# ADC.net
KiCad netlist of a schematic drawn in Altium Designer
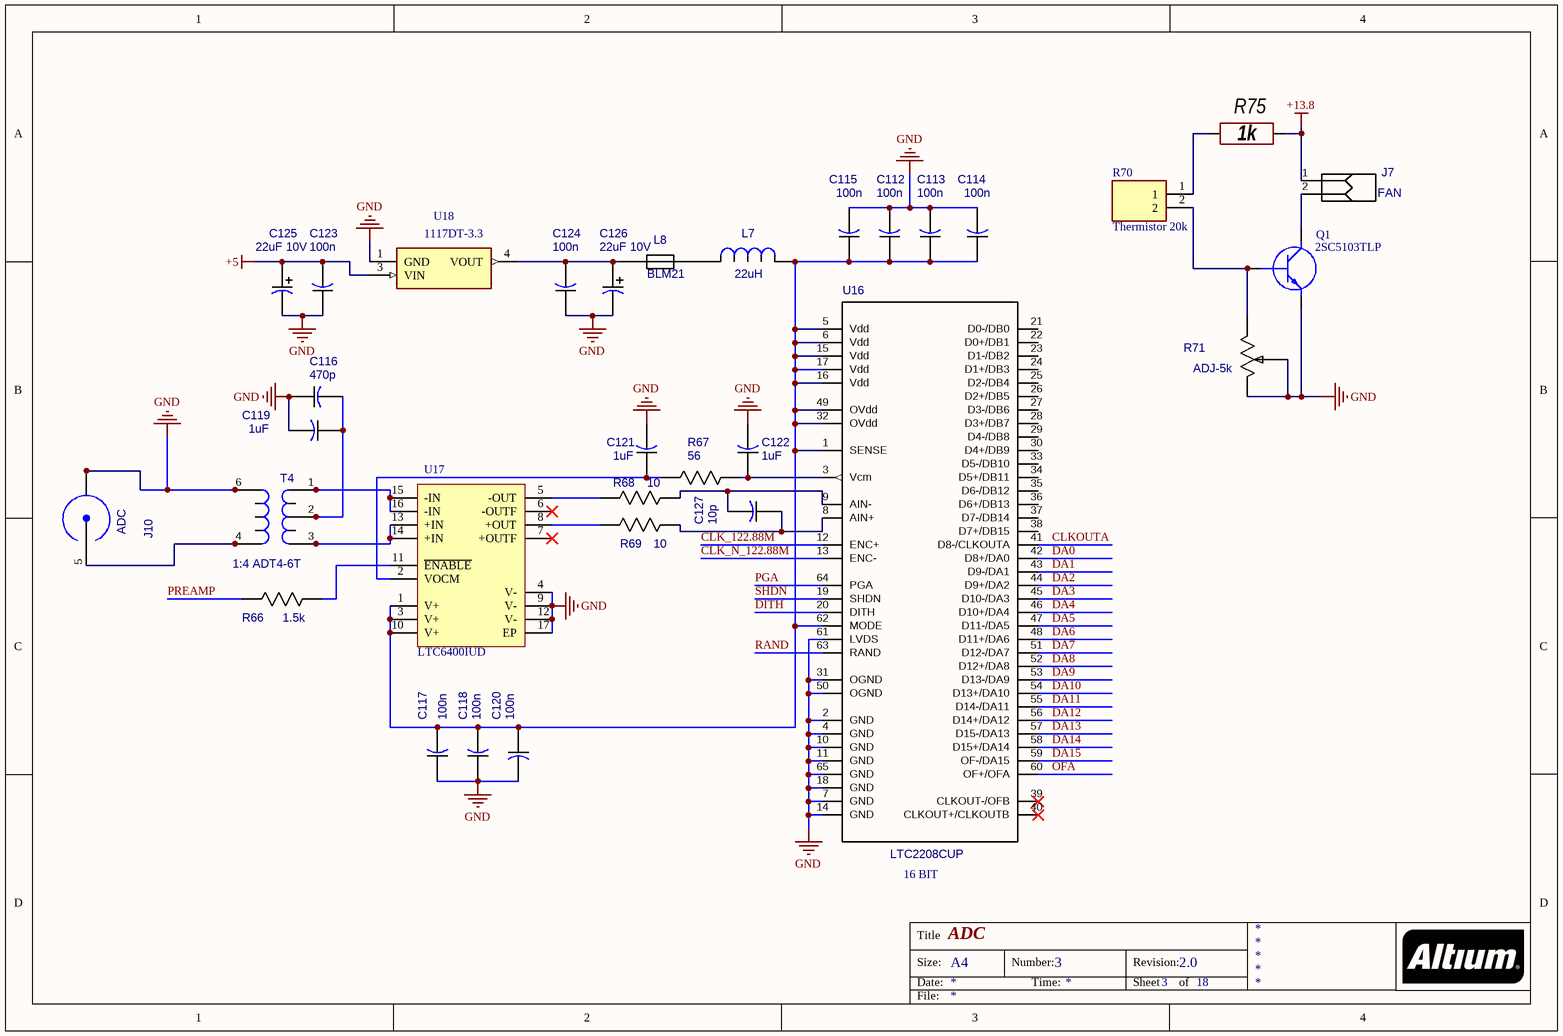
[diagram p0: ADC.SchDoc]

(export (version "E")
  (design (tool "Eeschema 10.0.6"))
  (components
    (comp (ref "C112")
      (value "100n")
      (footprint "CAP_0805")
      (description "CAP_0805")
      (libsource (lib "*") (part "CAP_0805"))
    )
    (comp (ref "C113")
      (value "100n")
      (footprint "CAP_0805")
      (description "CAP_0805")
      (libsource (lib "*") (part "CAP_0805"))
    )
    (comp (ref "C114")
      (value "100n")
      (footprint "CAP_0805")
      (description "CAP_0805")
      (libsource (lib "*") (part "CAP_0805"))
    )
    (comp (ref "C115")
      (value "100n")
      (footprint "CAP_0805")
      (description "CAP_0805")
      (libsource (lib "*") (part "CAP_0805"))
    )
    (comp (ref "C116")
      (value "470p")
      (footprint "CAP_0805")
      (description "CAP_0805")
      (libsource (lib "*") (part "CAP_0805"))
    )
    (comp (ref "C117")
      (value "100n")
      (footprint "CAP_0805")
      (description "CAP_0805")
      (libsource (lib "*") (part "CAP_0805"))
    )
    (comp (ref "C118")
      (value "100n")
      (footprint "CAP_0805")
      (description "CAP_0805")
      (libsource (lib "*") (part "CAP_0805"))
    )
    (comp (ref "C119")
      (value "1uF")
      (footprint "CAP_0805")
      (description "CAP_0805")
      (libsource (lib "*") (part "CAP_0805"))
    )
    (comp (ref "C120")
      (value "100n")
      (footprint "CAP_0805")
      (description "CAP_0805")
      (libsource (lib "*") (part "CAP_0805"))
    )
    (comp (ref "C121")
      (value "1uF")
      (footprint "CAP_0805")
      (description "CAP_0805")
      (libsource (lib "*") (part "CAP_0805"))
    )
    (comp (ref "C122")
      (value "1uF")
      (footprint "CAP_0805")
      (description "CAP_0805")
      (libsource (lib "*") (part "CAP_0805"))
    )
    (comp (ref "C123")
      (value "100n")
      (footprint "CAP_0805")
      (description "CAP_0805")
      (libsource (lib "*") (part "CAP_0805"))
    )
    (comp (ref "C124")
      (value "100n")
      (footprint "CAP_0805")
      (description "CAP_0805")
      (libsource (lib "*") (part "CAP_0805"))
    )
    (comp (ref "C125")
      (value "22uF 10V")
      (footprint "CAPAE_4.3x4.3h5.4")
      (description "CAPAE_4.3x4.3h5.4")
      (libsource (lib "MOTHERBOARD") (part "CAPAE_4.3x4.3h5.4"))
    )
    (comp (ref "C126")
      (value "22uF 10V")
      (footprint "CAPAE_4.3x4.3h5.4")
      (description "CAPAE_4.3x4.3h5.4")
      (libsource (lib "MOTHERBOARD") (part "CAPAE_4.3x4.3h5.4"))
    )
    (comp (ref "C127")
      (value "10p")
      (footprint "CAP_0805")
      (description "CAP_0805")
      (libsource (lib "*") (part "CAP_0805"))
    )
    (comp (ref "J7")
      (value "FAN")
      (footprint "51022-0200")
      (description "51022-0200")
      (libsource (lib "*") (part "51022-0200"))
    )
    (comp (ref "J10")
      (value "ADC")
      (footprint "31-5431")
      (description "SMA")
      (libsource (lib "RF-UNIT_1") (part "31-5431"))
    )
    (comp (ref "L7")
      (value "22uH")
      (footprint "IND_7x7")
      (description "IND_1206")
      (libsource (lib "*") (part "IND_1206"))
    )
    (comp (ref "L8")
      (value "BLM21")
      (footprint "CAP_0805")
      (libsource (lib "MOTHERBOARD_1") (part "IND_FERRITE_BEAD"))
    )
    (comp (ref "Q1")
      (value "2SC5103TLP")
      (footprint "SamacSys:2SC5103TLQ")
      (description "Transistor BJT NPN")
      (fields (field (name "MOUSER PART NUMBER") "755-2SC5103TLP"))
      (libsource (lib "*") (part "2SC5103TLP"))
    )
    (comp (ref "R66")
      (value "1.5k")
      (footprint "RES_0805")
      (description "RES_0805")
      (libsource (lib "*") (part "RES_0805"))
    )
    (comp (ref "R67")
      (value "56")
      (footprint "RES_0805")
      (description "RES_0805")
      (libsource (lib "") (part "RES_0805_1"))
    )
    (comp (ref "R68")
      (value "10")
      (footprint "RES_0603")
      (description "RES_0603")
      (libsource (lib "*") (part "RES_0603"))
    )
    (comp (ref "R69")
      (value "10")
      (footprint "RES_0603")
      (description "RES_0603")
      (libsource (lib "*") (part "RES_0603"))
    )
    (comp (ref "R70")
      (value "Thermistor 20k")
      (footprint "MF52A103F3950A1")
      (description "Thermistor")
      (fields (field (name "MANUFACTURER_PART_NUMBER") "MF52A103F3950(A1)"))
      (libsource (lib "*") (part "MF52A103F3950_A1_"))
    )
    (comp (ref "R71")
      (value "ADJ-5k")
      (footprint "306J")
      (description "306J")
      (libsource (lib "*") (part "306J"))
    )
    (comp (ref "R75")
      (value "1k")
      (footprint "standard:CH0805R")
      (libsource (lib "Discrete") (part "Resistor"))
    )
    (comp (ref "T4")
      (value "1:4 ADT4-6T")
      (footprint "TRANSF_ACORE2")
      (description "Transformer")
      (libsource (lib "MOTHERBOARD_1") (part "TRANSF_ACORE2"))
    )
    (comp (ref "U16") (value "LTC2208CUP") (footprint "LTC2208CUP") (libsource (lib "*") (part "LTC2208CUP")))
    (comp (ref "U17")
      (value "LTC6400IUD")
      (footprint "LT-UD-16_N")
      (fields
        (field (name "MANUFACTURER") "Linear Technology")
        (field (name "LINEAR TECHNOLOGY PART NUMBER") "LTC6400-20")
        (field (name "PARTNUMBER") "LTC6400IUD-20#PBF")
      )
      (libsource (lib "Altium Content Vault") (part "LT-LTC640X-X-16"))
    )
    (comp (ref "U18")
      (value "1117DT-3.3")
      (footprint "SamacSys:TO228P991X238-3N")
      (description "LD1117DT-2.5 DPAK")
      (fields
        (field (name "MANUFACTURER_PART_NUMBER") "LM1117DT-ADJ")
        (field (name "MOUSER PART NUMBER") "926-LM1117DT-ADJ")
      )
      (libsource (lib "*") (part "LM1117DT-ADJ"))
    )
  )
  (nets
    (net (code "1") (name "+5") (class "Default")
      (node (ref "C123") (pin "2") (pinfunction "2_2") (pintype "passive"))
      (node (ref "C125") (pin "1") (pinfunction "PLUS_1") (pintype "passive"))
      (node (ref "U18") (pin "3") (pinfunction "VIN_3") (pintype "input"))
    )
    (net (code "2") (name "+13.8") (class "Default")
      (node (ref "J7") (pin "1") (pinfunction "1_1") (pintype "passive"))
      (node (ref "R75") (pin "2") (pinfunction "2_2") (pintype "passive"))
    )
    (net (code "3") (name "/CLKOUTA") (class "Default")
      (node (ref "U16") (pin "41") (pinfunction "D8-/CLKOUTA_41") (pintype "passive"))
    )
    (net (code "4") (name "/CLK_122.88M") (class "Default")
      (node (ref "U16") (pin "12") (pinfunction "ENC+_12") (pintype "passive"))
    )
    (net (code "5") (name "/CLK_N_122.88M") (class "Default")
      (node (ref "U16") (pin "13") (pinfunction "ENC-_13") (pintype "passive"))
    )
    (net (code "6") (name "/DA0") (class "Default")
      (node (ref "U16") (pin "42") (pinfunction "D8+/DA0_42") (pintype "passive"))
    )
    (net (code "7") (name "/DA1") (class "Default")
      (node (ref "U16") (pin "43") (pinfunction "D9-/DA1_43") (pintype "passive"))
    )
    (net (code "8") (name "/DA2") (class "Default")
      (node (ref "U16") (pin "44") (pinfunction "D9+/DA2_44") (pintype "passive"))
    )
    (net (code "9") (name "/DA3") (class "Default")
      (node (ref "U16") (pin "45") (pinfunction "D10-/DA3_45") (pintype "passive"))
    )
    (net (code "10") (name "/DA4") (class "Default")
      (node (ref "U16") (pin "46") (pinfunction "D10+/DA4_46") (pintype "passive"))
    )
    (net (code "11") (name "/DA5") (class "Default")
      (node (ref "U16") (pin "47") (pinfunction "D11-/DA5_47") (pintype "passive"))
    )
    (net (code "12") (name "/DA6") (class "Default")
      (node (ref "U16") (pin "48") (pinfunction "D11+/DA6_48") (pintype "passive"))
    )
    (net (code "13") (name "/DA7") (class "Default")
      (node (ref "U16") (pin "51") (pinfunction "D12-/DA7_51") (pintype "passive"))
    )
    (net (code "14") (name "/DA8") (class "Default")
      (node (ref "U16") (pin "52") (pinfunction "D12+/DA8_52") (pintype "passive"))
    )
    (net (code "15") (name "/DA9") (class "Default")
      (node (ref "U16") (pin "53") (pinfunction "D13-/DA9_53") (pintype "passive"))
    )
    (net (code "16") (name "/DA10") (class "Default")
      (node (ref "U16") (pin "54") (pinfunction "D13+/DA10_54") (pintype "passive"))
    )
    (net (code "17") (name "/DA11") (class "Default")
      (node (ref "U16") (pin "55") (pinfunction "D14-/DA11_55") (pintype "passive"))
    )
    (net (code "18") (name "/DA12") (class "Default")
      (node (ref "U16") (pin "56") (pinfunction "D14+/DA12_56") (pintype "passive"))
    )
    (net (code "19") (name "/DA13") (class "Default")
      (node (ref "U16") (pin "57") (pinfunction "D15-/DA13_57") (pintype "passive"))
    )
    (net (code "20") (name "/DA14") (class "Default")
      (node (ref "U16") (pin "58") (pinfunction "D15+/DA14_58") (pintype "passive"))
    )
    (net (code "21") (name "/DA15") (class "Default")
      (node (ref "U16") (pin "59") (pinfunction "OF-/DA15_59") (pintype "passive"))
    )
    (net (code "22") (name "/DITH") (class "Default")
      (node (ref "U16") (pin "20") (pinfunction "DITH_20") (pintype "passive"))
    )
    (net (code "23") (name "/OFA") (class "Default")
      (node (ref "U16") (pin "60") (pinfunction "OF+/OFA_60") (pintype "passive"))
    )
    (net (code "24") (name "/PGA") (class "Default")
      (node (ref "U16") (pin "64") (pinfunction "PGA_64") (pintype "passive"))
    )
    (net (code "25") (name "/PREAMP") (class "Default")
      (node (ref "R66") (pin "2") (pinfunction "1_2") (pintype "passive"))
    )
    (net (code "26") (name "/RAND") (class "Default")
      (node (ref "U16") (pin "63") (pinfunction "RAND_63") (pintype "passive"))
    )
    (net (code "27") (name "/SHDN") (class "Default")
      (node (ref "U16") (pin "19") (pinfunction "SHDN_19") (pintype "passive"))
    )
    (net (code "28") (name "GND") (class "Default")
      (node (ref "C112") (pin "2") (pinfunction "2_2") (pintype "passive"))
      (node (ref "C113") (pin "2") (pinfunction "2_2") (pintype "passive"))
      (node (ref "C114") (pin "2") (pinfunction "2_2") (pintype "passive"))
      (node (ref "C115") (pin "2") (pinfunction "2_2") (pintype "passive"))
      (node (ref "C116") (pin "1") (pinfunction "1_1") (pintype "passive"))
      (node (ref "C117") (pin "1") (pinfunction "1_1") (pintype "passive"))
      (node (ref "C118") (pin "1") (pinfunction "1_1") (pintype "passive"))
      (node (ref "C119") (pin "2") (pinfunction "2_2") (pintype "passive"))
      (node (ref "C120") (pin "2") (pinfunction "2_2") (pintype "passive"))
      (node (ref "C121") (pin "2") (pinfunction "2_2") (pintype "passive"))
      (node (ref "C122") (pin "2") (pinfunction "2_2") (pintype "passive"))
      (node (ref "C123") (pin "1") (pinfunction "1_1") (pintype "passive"))
      (node (ref "C124") (pin "1") (pinfunction "1_1") (pintype "passive"))
      (node (ref "C125") (pin "2") (pinfunction "MINUS_2") (pintype "passive"))
      (node (ref "C126") (pin "2") (pinfunction "MINUS_2") (pintype "passive"))
      (node (ref "J10") (pin "1") (pinfunction "GND_1") (pintype "passive"))
      (node (ref "J10") (pin "2") (pinfunction "GND_2") (pintype "passive"))
      (node (ref "J10") (pin "3") (pinfunction "GND_3") (pintype "passive"))
      (node (ref "J10") (pin "4") (pinfunction "GND_4") (pintype "passive"))
      (node (ref "Q1") (pin "3") (pinfunction "E_3") (pintype "passive"))
      (node (ref "R71") (pin "1") (pinfunction "CCW_1") (pintype "passive"))
      (node (ref "R71") (pin "2") (pinfunction "W_2") (pintype "passive"))
      (node (ref "T4") (pin "10") (pinfunction "0_10") (pintype "passive"))
      (node (ref "T4") (pin "6") (pinfunction "P2_6") (pintype "passive"))
      (node (ref "U16") (pin "10") (pinfunction "GND_10") (pintype "passive"))
      (node (ref "U16") (pin "11") (pinfunction "GND_11") (pintype "passive"))
      (node (ref "U16") (pin "14") (pinfunction "GND_14") (pintype "passive"))
      (node (ref "U16") (pin "18") (pinfunction "GND_18") (pintype "passive"))
      (node (ref "U16") (pin "2") (pinfunction "GND_2") (pintype "passive"))
      (node (ref "U16") (pin "31") (pinfunction "OGND_31") (pintype "passive"))
      (node (ref "U16") (pin "4") (pinfunction "GND_4") (pintype "passive"))
      (node (ref "U16") (pin "50") (pinfunction "OGND_50") (pintype "passive"))
      (node (ref "U16") (pin "61") (pinfunction "LVDS_61") (pintype "passive"))
      (node (ref "U16") (pin "65") (pinfunction "GND_65") (pintype "passive"))
      (node (ref "U16") (pin "7") (pinfunction "GND_7") (pintype "passive"))
      (node (ref "U17") (pin "12") (pinfunction "V-_12") (pintype "power_in"))
      (node (ref "U17") (pin "17") (pinfunction "EP_17") (pintype "power_in"))
      (node (ref "U17") (pin "4") (pinfunction "V-_4") (pintype "power_in"))
      (node (ref "U17") (pin "9") (pinfunction "V-_9") (pintype "power_in"))
      (node (ref "U18") (pin "1") (pinfunction "GND_1") (pintype "passive"))
    )
    (net (code "29") (name "Net-(C126-PLUS)") (class "Default")
      (node (ref "C124") (pin "2") (pinfunction "2_2") (pintype "passive"))
      (node (ref "C126") (pin "1") (pinfunction "PLUS_1") (pintype "passive"))
      (node (ref "L8") (pin "1") (pinfunction "1_1") (pintype "passive"))
      (node (ref "U18") (pin "4") (pinfunction "VOUT_4") (pintype "output"))
    )
    (net (code "30") (name "Net-(J10-CON)") (class "Default")
      (node (ref "J10") (pin "5") (pinfunction "CON_5") (pintype "passive"))
      (node (ref "T4") (pin "11") (pinfunction "0_11") (pintype "passive"))
      (node (ref "T4") (pin "4") (pinfunction "P1_4") (pintype "passive"))
    )
    (net (code "31") (name "Net-(L7-Pad1)") (class "Default")
      (node (ref "L7") (pin "1") (pinfunction "1_1") (pintype "passive"))
      (node (ref "L8") (pin "2") (pinfunction "2_2") (pintype "passive"))
    )
    (net (code "32") (name "Net-(Q1-B)") (class "Default")
      (node (ref "Q1") (pin "1") (pinfunction "B_1") (pintype "passive"))
      (node (ref "R70") (pin "2") (pinfunction "2_2") (pintype "passive"))
      (node (ref "R71") (pin "3") (pinfunction "CW_3") (pintype "passive"))
    )
    (net (code "33") (name "Net-(Q1-C)") (class "Default")
      (node (ref "J7") (pin "2") (pinfunction "2_2") (pintype "passive"))
      (node (ref "Q1") (pin "2") (pinfunction "C_2") (pintype "passive"))
    )
    (net (code "34") (name "Net-(R66-2)") (class "Default")
      (node (ref "R66") (pin "1") (pinfunction "2_1") (pintype "passive"))
      (node (ref "U17") (pin "11") (pinfunction "~{ENABLE}_11") (pintype "passive"))
    )
    (net (code "35") (name "Net-(R70-Pad1)") (class "Default")
      (node (ref "R70") (pin "1") (pinfunction "1_1") (pintype "passive"))
      (node (ref "R75") (pin "1") (pinfunction "1_1") (pintype "passive"))
    )
    (net (code "36") (name "Net-(T4-S1)") (class "Default")
      (node (ref "T4") (pin "3") (pinfunction "S1_3") (pintype "passive"))
      (node (ref "T4") (pin "9") (pinfunction "0_9") (pintype "passive"))
      (node (ref "U17") (pin "13") (pinfunction "+IN_13") (pintype "passive"))
      (node (ref "U17") (pin "14") (pinfunction "+IN_14") (pintype "passive"))
    )
    (net (code "37") (name "Net-(T4-S2)") (class "Default")
      (node (ref "C116") (pin "2") (pinfunction "2_2") (pintype "passive"))
      (node (ref "C119") (pin "1") (pinfunction "1_1") (pintype "passive"))
      (node (ref "T4") (pin "2") (pinfunction "S2_2") (pintype "passive"))
      (node (ref "T4") (pin "8") (pinfunction "0_8") (pintype "passive"))
    )
    (net (code "38") (name "Net-(T4-S3)") (class "Default")
      (node (ref "T4") (pin "1") (pinfunction "S3_1") (pintype "passive"))
      (node (ref "T4") (pin "7") (pinfunction "0_7") (pintype "passive"))
      (node (ref "U17") (pin "15") (pinfunction "-IN_15") (pintype "passive"))
      (node (ref "U17") (pin "16") (pinfunction "-IN_16") (pintype "passive"))
    )
    (net (code "39") (name "Net-(U16-AIN+)") (class "Default")
      (node (ref "C127") (pin "1") (pinfunction "1_1") (pintype "passive"))
      (node (ref "R69") (pin "2") (pinfunction "2_2") (pintype "passive"))
      (node (ref "U16") (pin "8") (pinfunction "AIN+_8") (pintype "passive"))
    )
    (net (code "40") (name "Net-(U16-AIN-)") (class "Default")
      (node (ref "C127") (pin "2") (pinfunction "2_2") (pintype "passive"))
      (node (ref "R68") (pin "2") (pinfunction "2_2") (pintype "passive"))
      (node (ref "U16") (pin "9") (pinfunction "AIN-_9") (pintype "passive"))
    )
    (net (code "41") (name "Net-(U16-MODE)") (class "Default")
      (node (ref "C112") (pin "1") (pinfunction "1_1") (pintype "passive"))
      (node (ref "C113") (pin "1") (pinfunction "1_1") (pintype "passive"))
      (node (ref "C114") (pin "1") (pinfunction "1_1") (pintype "passive"))
      (node (ref "C115") (pin "1") (pinfunction "1_1") (pintype "passive"))
      (node (ref "C117") (pin "2") (pinfunction "2_2") (pintype "passive"))
      (node (ref "C118") (pin "2") (pinfunction "2_2") (pintype "passive"))
      (node (ref "C120") (pin "1") (pinfunction "1_1") (pintype "passive"))
      (node (ref "L7") (pin "2") (pinfunction "2_2") (pintype "passive"))
      (node (ref "U16") (pin "1") (pinfunction "SENSE_1") (pintype "passive"))
      (node (ref "U16") (pin "15") (pinfunction "Vdd_15") (pintype "passive"))
      (node (ref "U16") (pin "16") (pinfunction "Vdd_16") (pintype "passive"))
      (node (ref "U16") (pin "17") (pinfunction "Vdd_17") (pintype "passive"))
      (node (ref "U16") (pin "32") (pinfunction "OVdd_32") (pintype "passive"))
      (node (ref "U16") (pin "49") (pinfunction "OVdd_49") (pintype "passive"))
      (node (ref "U16") (pin "5") (pinfunction "Vdd_5") (pintype "passive"))
      (node (ref "U16") (pin "6") (pinfunction "Vdd_6") (pintype "passive"))
      (node (ref "U16") (pin "62") (pinfunction "MODE_62") (pintype "passive"))
      (node (ref "U17") (pin "1") (pinfunction "V+_1") (pintype "power_in"))
      (node (ref "U17") (pin "10") (pinfunction "V+_10") (pintype "power_in"))
      (node (ref "U17") (pin "3") (pinfunction "V+_3") (pintype "power_in"))
    )
    (net (code "42") (name "Net-(U16-Vcm)") (class "Default")
      (node (ref "C122") (pin "1") (pinfunction "1_1") (pintype "passive"))
      (node (ref "R67") (pin "2") (pinfunction "2_2") (pintype "passive"))
      (node (ref "U16") (pin "3") (pinfunction "Vcm_3") (pintype "output"))
    )
    (net (code "43") (name "Net-(U17-+OUT)") (class "Default")
      (node (ref "R69") (pin "1") (pinfunction "1_1") (pintype "passive"))
      (node (ref "U17") (pin "8") (pinfunction "+OUT_8") (pintype "passive"))
    )
    (net (code "44") (name "Net-(U17--OUT)") (class "Default")
      (node (ref "R68") (pin "1") (pinfunction "1_1") (pintype "passive"))
      (node (ref "U17") (pin "5") (pinfunction "-OUT_5") (pintype "passive"))
    )
    (net (code "45") (name "Net-(U17-VOCM)") (class "Default")
      (node (ref "C121") (pin "1") (pinfunction "1_1") (pintype "passive"))
      (node (ref "R67") (pin "1") (pinfunction "1_1") (pintype "passive"))
      (node (ref "U17") (pin "2") (pinfunction "VOCM_2") (pintype "passive"))
    )
    (net (code "46") (name "unconnected-(U16-CLKOUT+{slash}CLKOUTB-Pad40)") (class "Default")
      (node (ref "U16") (pin "40") (pinfunction "CLKOUT+/CLKOUTB_40") (pintype "passive+no_connect"))
    )
    (net (code "47") (name "unconnected-(U16-CLKOUT-{slash}OFB-Pad39)") (class "Default")
      (node (ref "U16") (pin "39") (pinfunction "CLKOUT-/OFB_39") (pintype "passive+no_connect"))
    )
    (net (code "48") (name "unconnected-(U16-D0+{slash}DB1-Pad22)") (class "Default")
      (node (ref "U16") (pin "22") (pinfunction "D0+/DB1_22") (pintype "passive"))
    )
    (net (code "49") (name "unconnected-(U16-D0-{slash}DB0-Pad21)") (class "Default")
      (node (ref "U16") (pin "21") (pinfunction "D0-/DB0_21") (pintype "passive"))
    )
    (net (code "50") (name "unconnected-(U16-D1+{slash}DB3-Pad24)") (class "Default")
      (node (ref "U16") (pin "24") (pinfunction "D1+/DB3_24") (pintype "passive"))
    )
    (net (code "51") (name "unconnected-(U16-D1-{slash}DB2-Pad23)") (class "Default")
      (node (ref "U16") (pin "23") (pinfunction "D1-/DB2_23") (pintype "passive"))
    )
    (net (code "52") (name "unconnected-(U16-D2+{slash}DB5-Pad26)") (class "Default")
      (node (ref "U16") (pin "26") (pinfunction "D2+/DB5_26") (pintype "passive"))
    )
    (net (code "53") (name "unconnected-(U16-D2-{slash}DB4-Pad25)") (class "Default")
      (node (ref "U16") (pin "25") (pinfunction "D2-/DB4_25") (pintype "passive"))
    )
    (net (code "54") (name "unconnected-(U16-D3+{slash}DB7-Pad28)") (class "Default")
      (node (ref "U16") (pin "28") (pinfunction "D3+/DB7_28") (pintype "passive"))
    )
    (net (code "55") (name "unconnected-(U16-D3-{slash}DB6-Pad27)") (class "Default")
      (node (ref "U16") (pin "27") (pinfunction "D3-/DB6_27") (pintype "passive"))
    )
    (net (code "56") (name "unconnected-(U16-D4+{slash}DB9-Pad30)") (class "Default")
      (node (ref "U16") (pin "30") (pinfunction "D4+/DB9_30") (pintype "passive"))
    )
    (net (code "57") (name "unconnected-(U16-D4-{slash}DB8-Pad29)") (class "Default")
      (node (ref "U16") (pin "29") (pinfunction "D4-/DB8_29") (pintype "passive"))
    )
    (net (code "58") (name "unconnected-(U16-D5+{slash}DB11-Pad34)") (class "Default")
      (node (ref "U16") (pin "34") (pinfunction "D5+/DB11_34") (pintype "passive"))
    )
    (net (code "59") (name "unconnected-(U16-D5-{slash}DB10-Pad33)") (class "Default")
      (node (ref "U16") (pin "33") (pinfunction "D5-/DB10_33") (pintype "passive"))
    )
    (net (code "60") (name "unconnected-(U16-D6+{slash}DB13-Pad36)") (class "Default")
      (node (ref "U16") (pin "36") (pinfunction "D6+/DB13_36") (pintype "passive"))
    )
    (net (code "61") (name "unconnected-(U16-D6-{slash}DB12-Pad35)") (class "Default")
      (node (ref "U16") (pin "35") (pinfunction "D6-/DB12_35") (pintype "passive"))
    )
    (net (code "62") (name "unconnected-(U16-D7+{slash}DB15-Pad38)") (class "Default")
      (node (ref "U16") (pin "38") (pinfunction "D7+/DB15_38") (pintype "passive"))
    )
    (net (code "63") (name "unconnected-(U16-D7-{slash}DB14-Pad37)") (class "Default")
      (node (ref "U16") (pin "37") (pinfunction "D7-/DB14_37") (pintype "passive"))
    )
    (net (code "64") (name "unconnected-(U17-+OUTF-Pad7)") (class "Default")
      (node (ref "U17") (pin "7") (pinfunction "+OUTF_7") (pintype "passive+no_connect"))
    )
    (net (code "65") (name "unconnected-(U17--OUTF-Pad6)") (class "Default")
      (node (ref "U17") (pin "6") (pinfunction "-OUTF_6") (pintype "passive+no_connect"))
    )
  )
)
